# MyRIO_Breakout_Gamma2b.net
KiCad netlist of a schematic drawn in EAGLE
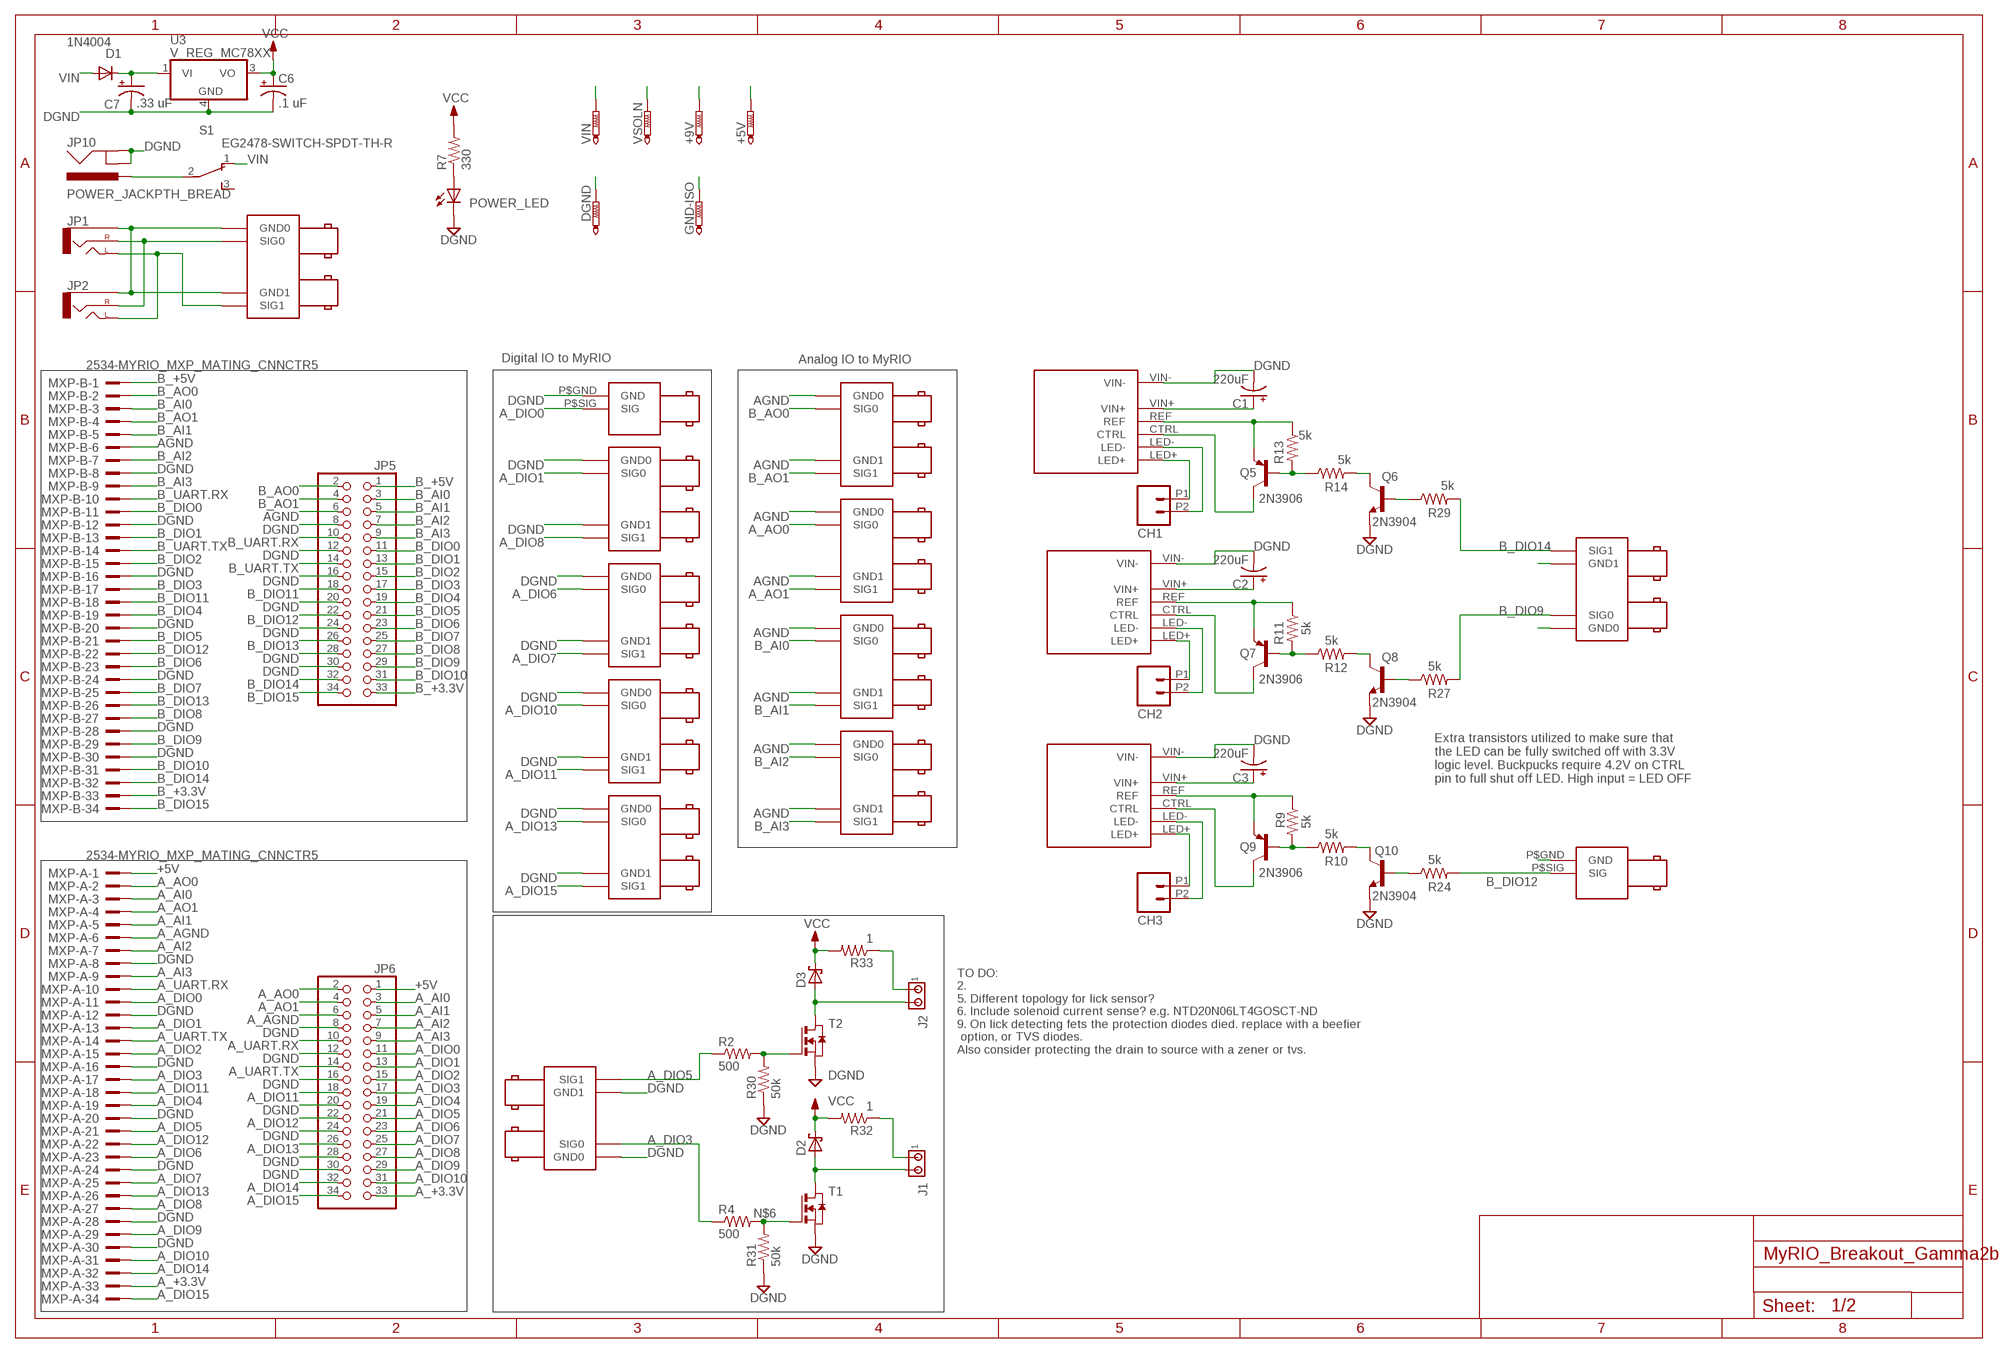
[diagram p0: schematic, sheet 1]
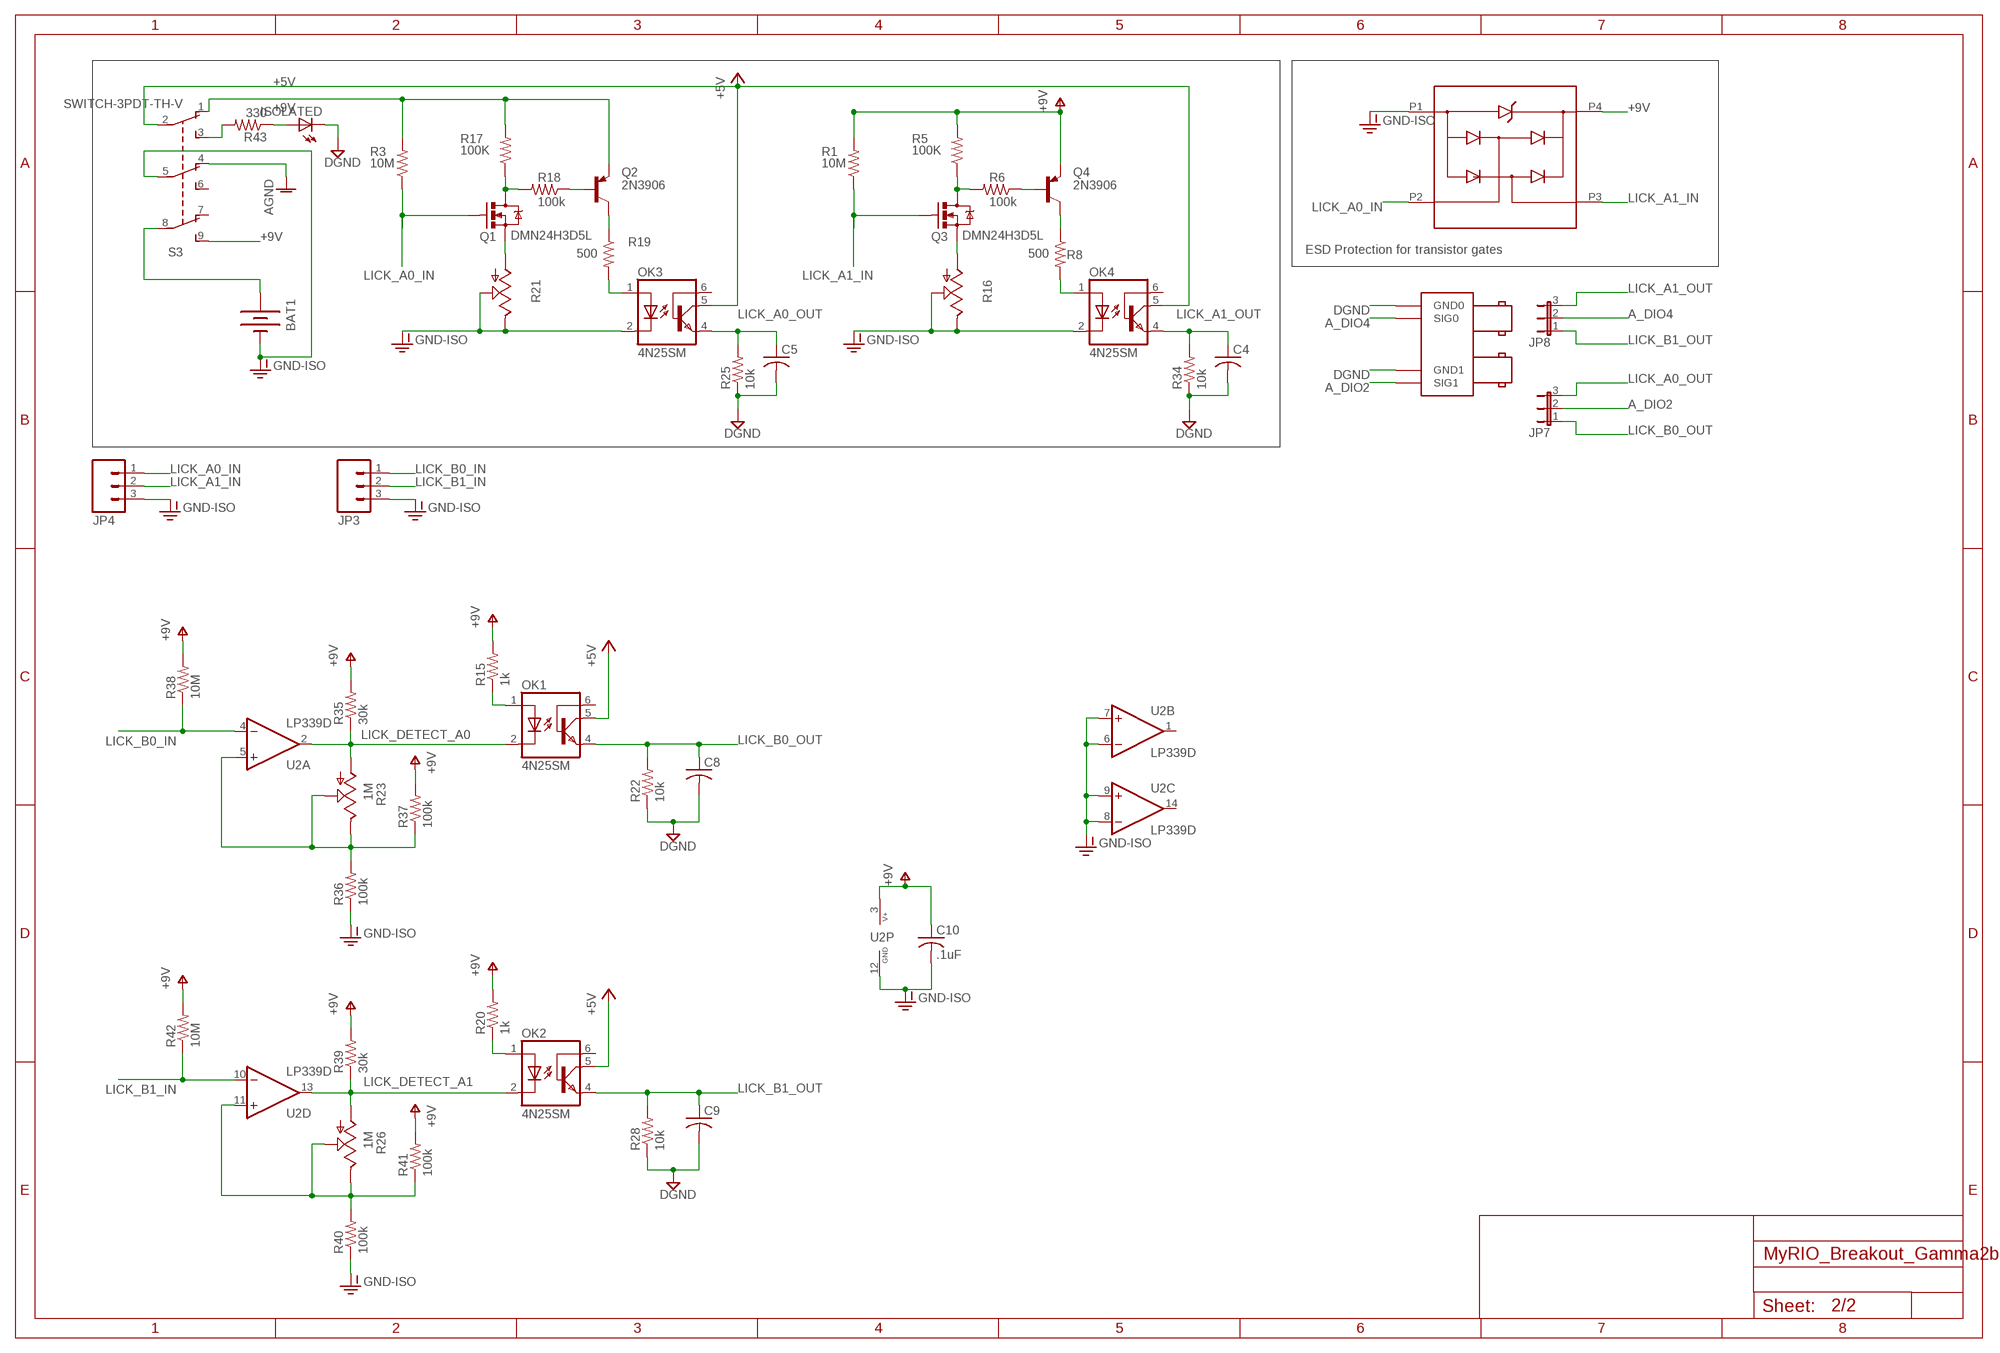
[diagram p1: schematic, sheet 2]

(export (version "E")
  (design (tool "Eeschema 10.0.6"))
  (components
    (comp (ref "BAT1")
      (value "BATTERY9V")
      (footprint "eagle-import:BATTCON_9V")
      (libsource (lib "eagle-import") (part "BATTERY9V"))
    )
    (comp (ref "C4")
      (value "C-US025-024X044")
      (footprint "eagle-import:C025-024X044")
      (libsource (lib "eagle-import") (part "C-US025-024X044"))
    )
    (comp (ref "C5")
      (value "C-US025-024X044")
      (footprint "eagle-import:C025-024X044")
      (libsource (lib "eagle-import") (part "C-US025-024X044"))
    )
    (comp (ref "C8")
      (value "C-US025-024X044")
      (footprint "eagle-import:C025-024X044")
      (libsource (lib "eagle-import") (part "C-US025-024X044"))
    )
    (comp (ref "C9")
      (value "C-US025-024X044")
      (footprint "eagle-import:C025-024X044")
      (libsource (lib "eagle-import") (part "C-US025-024X044"))
    )
    (comp (ref "C10")
      (value ".1uF")
      (footprint "eagle-import:C0805K")
      (libsource (lib "eagle-import") (part "C-USC0805K"))
    )
    (comp (ref "ISOLATED")
      (value "LED3MM")
      (footprint "eagle-import:LED3MM")
      (libsource (lib "eagle-import") (part "LED3MM"))
    )
    (comp (ref "JP3")
      (value "M03POLAR")
      (footprint "eagle-import:MOLEX-1X3")
      (libsource (lib "eagle-import") (part "M03POLAR"))
    )
    (comp (ref "JP4")
      (value "M03POLAR")
      (footprint "eagle-import:MOLEX-1X3")
      (libsource (lib "eagle-import") (part "M03POLAR"))
    )
    (comp (ref "JP7")
      (value "JP2E")
      (footprint "eagle-import:JP2")
      (libsource (lib "eagle-import") (part "JP2E"))
    )
    (comp (ref "JP8")
      (value "JP2E")
      (footprint "eagle-import:JP2")
      (libsource (lib "eagle-import") (part "JP2E"))
    )
    (comp (ref "LICK")
      (value "BNC_RIGHT_ANGLE_DOUBLE")
      (footprint "eagle-import:BNC_RIGHT_ANGLE_DOUBLE")
      (libsource (lib "eagle-import") (part "BNC_RIGHT_ANGLE_DOUBLE"))
    )
    (comp (ref "OK1")
      (value "4N25SM")
      (footprint "eagle-import:DIL6-SMD")
      (fields (field (name "MF") "FAIRCHILD SEMICONDUCTOR"))
      (libsource (lib "eagle-import") (part "4N?MS25"))
    )
    (comp (ref "OK2")
      (value "4N25SM")
      (footprint "eagle-import:DIL6-SMD")
      (fields (field (name "MF") "FAIRCHILD SEMICONDUCTOR"))
      (libsource (lib "eagle-import") (part "4N?MS25"))
    )
    (comp (ref "OK3")
      (value "4N25SM")
      (footprint "eagle-import:DIL6-SMD")
      (fields (field (name "MF") "FAIRCHILD SEMICONDUCTOR"))
      (libsource (lib "eagle-import") (part "4N?MS25"))
    )
    (comp (ref "OK4")
      (value "4N25SM")
      (footprint "eagle-import:DIL6-SMD")
      (fields (field (name "MF") "FAIRCHILD SEMICONDUCTOR"))
      (libsource (lib "eagle-import") (part "4N?MS25"))
    )
    (comp (ref "Q1")
      (value "DMN24H3D5L")
      (footprint "eagle-import:SOT23-3")
      (libsource (lib "eagle-import") (part "MOSFET-NCHANNELAO3404A"))
    )
    (comp (ref "Q2")
      (value "2N3906")
      (footprint "eagle-import:SOT23-BEC")
      (libsource (lib "eagle-import") (part "-PNP-SOT23-BECMMBT3906LT1"))
    )
    (comp (ref "Q3")
      (value "DMN24H3D5L")
      (footprint "eagle-import:SOT23-3")
      (libsource (lib "eagle-import") (part "MOSFET-NCHANNELAO3404A"))
    )
    (comp (ref "Q4")
      (value "2N3906")
      (footprint "eagle-import:SOT23-BEC")
      (libsource (lib "eagle-import") (part "-PNP-SOT23-BECMMBT3906LT1"))
    )
    (comp (ref "R1")
      (value "10M")
      (footprint "eagle-import:0805S")
      (libsource (lib "eagle-import") (part "RESISTOR_SM0805S"))
    )
    (comp (ref "R3")
      (value "10M")
      (footprint "eagle-import:0805S")
      (libsource (lib "eagle-import") (part "RESISTOR_SM0805S"))
    )
    (comp (ref "R5")
      (value "100K")
      (footprint "eagle-import:0805S")
      (libsource (lib "eagle-import") (part "RESISTOR_SM0805S"))
    )
    (comp (ref "R6")
      (value "100k")
      (footprint "eagle-import:0805S")
      (libsource (lib "eagle-import") (part "RESISTOR_SM0805S"))
    )
    (comp (ref "R8")
      (value "500")
      (footprint "eagle-import:0805S")
      (libsource (lib "eagle-import") (part "RESISTOR_SM0805S"))
    )
    (comp (ref "R15")
      (value "1k")
      (footprint "eagle-import:M0805")
      (libsource (lib "eagle-import") (part "R-US_M0805"))
    )
    (comp (ref "R16")
      (value "TRIM_US-B25P")
      (footprint "eagle-import:B25P")
      (libsource (lib "eagle-import") (part "TRIM_US-B25P"))
    )
    (comp (ref "R17")
      (value "100K")
      (footprint "eagle-import:0805S")
      (libsource (lib "eagle-import") (part "RESISTOR_SM0805S"))
    )
    (comp (ref "R18")
      (value "100k")
      (footprint "eagle-import:0805S")
      (libsource (lib "eagle-import") (part "RESISTOR_SM0805S"))
    )
    (comp (ref "R19")
      (value "500")
      (footprint "eagle-import:0805S")
      (libsource (lib "eagle-import") (part "RESISTOR_SM0805S"))
    )
    (comp (ref "R20")
      (value "1k")
      (footprint "eagle-import:M0805")
      (libsource (lib "eagle-import") (part "R-US_M0805"))
    )
    (comp (ref "R21")
      (value "TRIM_US-B25P")
      (footprint "eagle-import:B25P")
      (libsource (lib "eagle-import") (part "TRIM_US-B25P"))
    )
    (comp (ref "R22")
      (value "10k")
      (footprint "eagle-import:0204V")
      (libsource (lib "eagle-import") (part "R-US_0204/2V"))
    )
    (comp (ref "R23")
      (value "1M")
      (footprint "eagle-import:B25P")
      (libsource (lib "eagle-import") (part "TRIM_US-B25P"))
    )
    (comp (ref "R25")
      (value "10k")
      (footprint "eagle-import:0204V")
      (libsource (lib "eagle-import") (part "R-US_0204/2V"))
    )
    (comp (ref "R26")
      (value "1M")
      (footprint "eagle-import:B25P")
      (libsource (lib "eagle-import") (part "TRIM_US-B25P"))
    )
    (comp (ref "R28")
      (value "10k")
      (footprint "eagle-import:0204V")
      (libsource (lib "eagle-import") (part "R-US_0204/2V"))
    )
    (comp (ref "R34")
      (value "10k")
      (footprint "eagle-import:0204V")
      (libsource (lib "eagle-import") (part "R-US_0204/2V"))
    )
    (comp (ref "R35")
      (value "30k")
      (footprint "eagle-import:M0805")
      (libsource (lib "eagle-import") (part "R-US_M0805"))
    )
    (comp (ref "R36")
      (value "100k")
      (footprint "eagle-import:M0805")
      (libsource (lib "eagle-import") (part "R-US_M0805"))
    )
    (comp (ref "R37")
      (value "100k")
      (footprint "eagle-import:M0805")
      (libsource (lib "eagle-import") (part "R-US_M0805"))
    )
    (comp (ref "R38")
      (value "10M")
      (footprint "eagle-import:M0805")
      (libsource (lib "eagle-import") (part "R-US_M0805"))
    )
    (comp (ref "R39")
      (value "30k")
      (footprint "eagle-import:M0805")
      (libsource (lib "eagle-import") (part "R-US_M0805"))
    )
    (comp (ref "R40")
      (value "100k")
      (footprint "eagle-import:M0805")
      (libsource (lib "eagle-import") (part "R-US_M0805"))
    )
    (comp (ref "R41")
      (value "100k")
      (footprint "eagle-import:M0805")
      (libsource (lib "eagle-import") (part "R-US_M0805"))
    )
    (comp (ref "R42")
      (value "10M")
      (footprint "eagle-import:M0805")
      (libsource (lib "eagle-import") (part "R-US_M0805"))
    )
    (comp (ref "R43")
      (value "330")
      (footprint "eagle-import:0207_10")
      (libsource (lib "eagle-import") (part "R-US_0207/10"))
    )
    (comp (ref "S3")
      (value "SWITCH-3PDT-TH-V")
      (footprint "eagle-import:NKK-M20-9PIN-VERTICAL")
      (libsource (lib "eagle-import") (part "SWITCH-3PDT-TH-V"))
    )
    (comp (ref "U1")
      (value "CD143A-12_TVS")
      (footprint "eagle-import:SOT-143")
      (libsource (lib "eagle-import") (part "CD143A-12_TVS"))
    )
    (comp (ref "U2")
      (value "LP339D")
      (footprint "eagle-import:SO14")
      (libsource (lib "eagle-import") (part "LM339D"))
    )
    (comp (ref "+5V")
      (value "PTR1PAD1-17Y")
      (footprint "eagle-import:P1-17Y")
      (libsource (lib "eagle-import") (part "PTR1PAD1-17Y"))
    )
    (comp (ref "+9V")
      (value "PTR1PAD1-17Y")
      (footprint "eagle-import:P1-17Y")
      (libsource (lib "eagle-import") (part "PTR1PAD1-17Y"))
    )
    (comp (ref "AAO_0,1")
      (value "BNC_RIGHT_ANGLE_DOUBLE")
      (footprint "eagle-import:BNC_RIGHT_ANGLE_DOUBLE")
      (libsource (lib "eagle-import") (part "BNC_RIGHT_ANGLE_DOUBLE"))
    )
    (comp (ref "ACTV_REC")
      (value "BNC_RIGHT_ANGLE")
      (footprint "eagle-import:BNC_RIGHT_ANGLE")
      (libsource (lib "eagle-import") (part "BNC_RIGHT_ANGLE"))
    )
    (comp (ref "AUDIO")
      (value "BNC_RIGHT_ANGLE_DOUBLE")
      (footprint "eagle-import:BNC_RIGHT_ANGLE_DOUBLE")
      (libsource (lib "eagle-import") (part "BNC_RIGHT_ANGLE_DOUBLE"))
    )
    (comp (ref "BAI_0,1")
      (value "BNC_RIGHT_ANGLE_DOUBLE")
      (footprint "eagle-import:BNC_RIGHT_ANGLE_DOUBLE")
      (libsource (lib "eagle-import") (part "BNC_RIGHT_ANGLE_DOUBLE"))
    )
    (comp (ref "BAI_2,3")
      (value "BNC_RIGHT_ANGLE_DOUBLE")
      (footprint "eagle-import:BNC_RIGHT_ANGLE_DOUBLE")
      (libsource (lib "eagle-import") (part "BNC_RIGHT_ANGLE_DOUBLE"))
    )
    (comp (ref "BAO_0,1")
      (value "BNC_RIGHT_ANGLE_DOUBLE")
      (footprint "eagle-import:BNC_RIGHT_ANGLE_DOUBLE")
      (libsource (lib "eagle-import") (part "BNC_RIGHT_ANGLE_DOUBLE"))
    )
    (comp (ref "BUCKPUCK1")
      (value "BUCKPUCK-350-I")
      (footprint "eagle-import:BUCKPUCK_I")
      (libsource (lib "eagle-import") (part "BUCKPUCK--?I350"))
    )
    (comp (ref "BUCKPUCK2")
      (value "BUCKPUCK-350-I")
      (footprint "eagle-import:BUCKPUCK_I")
      (libsource (lib "eagle-import") (part "BUCKPUCK--?I350"))
    )
    (comp (ref "BUCKPUCK3")
      (value "BUCKPUCK-350-I")
      (footprint "eagle-import:BUCKPUCK_I")
      (libsource (lib "eagle-import") (part "BUCKPUCK--?I350"))
    )
    (comp (ref "C1")
      (value "220uF")
      (footprint "eagle-import:E5-10,5")
      (libsource (lib "eagle-import") (part "CPOL-USE5-10.5"))
    )
    (comp (ref "C2")
      (value "220uF")
      (footprint "eagle-import:E5-10,5")
      (libsource (lib "eagle-import") (part "CPOL-USE5-10.5"))
    )
    (comp (ref "C3")
      (value "220uF")
      (footprint "eagle-import:E5-10,5")
      (libsource (lib "eagle-import") (part "CPOL-USE5-10.5"))
    )
    (comp (ref "C6")
      (value ".1 uF")
      (footprint "eagle-import:E2,5-5")
      (libsource (lib "eagle-import") (part "CPOL-USE2.5-5"))
    )
    (comp (ref "C7")
      (value ".33 uF")
      (footprint "eagle-import:E2,5-5")
      (libsource (lib "eagle-import") (part "CPOL-USE2.5-5"))
    )
    (comp (ref "CAMERA")
      (value "BNC_RIGHT_ANGLE_DOUBLE")
      (footprint "eagle-import:BNC_RIGHT_ANGLE_DOUBLE")
      (libsource (lib "eagle-import") (part "BNC_RIGHT_ANGLE_DOUBLE"))
    )
    (comp (ref "CH1")
      (value "M022.54MM_SCREWTERM")
      (footprint "eagle-import:1X02_2.54_SCREWTERM")
      (libsource (lib "eagle-import") (part "M022.54MM_SCREWTERM"))
    )
    (comp (ref "CH2")
      (value "M022.54MM_SCREWTERM")
      (footprint "eagle-import:1X02_2.54_SCREWTERM")
      (libsource (lib "eagle-import") (part "M022.54MM_SCREWTERM"))
    )
    (comp (ref "CH3")
      (value "M022.54MM_SCREWTERM")
      (footprint "eagle-import:1X02_2.54_SCREWTERM")
      (libsource (lib "eagle-import") (part "M022.54MM_SCREWTERM"))
    )
    (comp (ref "D1")
      (value "1N4004")
      (footprint "eagle-import:DO41-10")
      (libsource (lib "eagle-import") (part "1N4004"))
    )
    (comp (ref "D2")
      (value "SCHOTTKY-DIODE")
      (footprint "eagle-import:DIODE_SMB")
      (libsource (lib "eagle-import") (part "SCHOTTKY-DIODE"))
    )
    (comp (ref "D3")
      (value "SCHOTTKY-DIODE")
      (footprint "eagle-import:DIODE_SMB")
      (libsource (lib "eagle-import") (part "SCHOTTKY-DIODE"))
    )
    (comp (ref "DGND")
      (value "PTR1PAD1-17Y")
      (footprint "eagle-import:P1-17Y")
      (libsource (lib "eagle-import") (part "PTR1PAD1-17Y"))
    )
    (comp (ref "D_FREE1_2")
      (value "BNC_RIGHT_ANGLE_DOUBLE")
      (footprint "eagle-import:BNC_RIGHT_ANGLE_DOUBLE")
      (libsource (lib "eagle-import") (part "BNC_RIGHT_ANGLE_DOUBLE"))
    )
    (comp (ref "D_FREE3_4")
      (value "BNC_RIGHT_ANGLE_DOUBLE")
      (footprint "eagle-import:BNC_RIGHT_ANGLE_DOUBLE")
      (libsource (lib "eagle-import") (part "BNC_RIGHT_ANGLE_DOUBLE"))
    )
    (comp (ref "GND-ISO")
      (value "PTR1PAD1-17Y")
      (footprint "eagle-import:P1-17Y")
      (libsource (lib "eagle-import") (part "PTR1PAD1-17Y"))
    )
    (comp (ref "J1")
      (value "MTA02-100")
      (footprint "eagle-import:10X02MTA")
      (libsource (lib "eagle-import") (part "MTA02-100"))
    )
    (comp (ref "J2")
      (value "MTA02-100")
      (footprint "eagle-import:10X02MTA")
      (libsource (lib "eagle-import") (part "MTA02-100"))
    )
    (comp (ref "JP1")
      (value "AUDIO-JACKPTH")
      (footprint "eagle-import:AUDIO-JACK")
      (libsource (lib "eagle-import") (part "AUDIO-JACKPTH"))
    )
    (comp (ref "JP2")
      (value "AUDIO-JACKPTH")
      (footprint "eagle-import:AUDIO-JACK")
      (libsource (lib "eagle-import") (part "AUDIO-JACKPTH"))
    )
    (comp (ref "JP5")
      (value "PINHD-2X17")
      (footprint "eagle-import:2X17")
      (libsource (lib "eagle-import") (part "PINHD-2X17"))
    )
    (comp (ref "JP6")
      (value "PINHD-2X17")
      (footprint "eagle-import:2X17")
      (libsource (lib "eagle-import") (part "PINHD-2X17"))
    )
    (comp (ref "JP10")
      (value "POWER_JACKPTH_BREAD")
      (footprint "eagle-import:POWER_JACK_PTH_BREAD")
      (libsource (lib "eagle-import") (part "POWER_JACKPTH_BREAD"))
    )
    (comp (ref "LED_CUE")
      (value "BNC_RIGHT_ANGLE")
      (footprint "eagle-import:BNC_RIGHT_ANGLE")
      (libsource (lib "eagle-import") (part "BNC_RIGHT_ANGLE"))
    )
    (comp (ref "LED_MASK")
      (value "BNC_RIGHT_ANGLE_DOUBLE")
      (footprint "eagle-import:BNC_RIGHT_ANGLE_DOUBLE")
      (libsource (lib "eagle-import") (part "BNC_RIGHT_ANGLE_DOUBLE"))
    )
    (comp (ref "MXP-A")
      (value "2534-MYRIO_MXP_MATING_CNNCTR5")
      (footprint "eagle-import:PAK100_2500-5-34-MXP_CONNCTR")
      (libsource (lib "eagle-import") (part "2534-MYRIO_MXP_MATING_CNNCTR5"))
    )
    (comp (ref "MXP-B")
      (value "2534-MYRIO_MXP_MATING_CNNCTR5")
      (footprint "eagle-import:PAK100_2500-5-34-MXP_CONNCTR")
      (libsource (lib "eagle-import") (part "2534-MYRIO_MXP_MATING_CNNCTR5"))
    )
    (comp (ref "POWER_LED")
      (value "LED3MM")
      (footprint "eagle-import:LED3MM")
      (libsource (lib "eagle-import") (part "LED3MM"))
    )
    (comp (ref "Q5")
      (value "2N3906")
      (footprint "eagle-import:SOT23-BEC")
      (libsource (lib "eagle-import") (part "-PNP-SOT23-BECMMBT3906LT1"))
    )
    (comp (ref "Q6")
      (value "2N3904")
      (footprint "eagle-import:SOT23-BEC")
      (libsource (lib "eagle-import") (part "-NPN-SOT23-BECMMBT3904LT1"))
    )
    (comp (ref "Q7")
      (value "2N3906")
      (footprint "eagle-import:SOT23-BEC")
      (libsource (lib "eagle-import") (part "-PNP-SOT23-BECMMBT3906LT1"))
    )
    (comp (ref "Q8")
      (value "2N3904")
      (footprint "eagle-import:SOT23-BEC")
      (libsource (lib "eagle-import") (part "-NPN-SOT23-BECMMBT3904LT1"))
    )
    (comp (ref "Q9")
      (value "2N3906")
      (footprint "eagle-import:SOT23-BEC")
      (libsource (lib "eagle-import") (part "-PNP-SOT23-BECMMBT3906LT1"))
    )
    (comp (ref "Q10")
      (value "2N3904")
      (footprint "eagle-import:SOT23-BEC")
      (libsource (lib "eagle-import") (part "-NPN-SOT23-BECMMBT3904LT1"))
    )
    (comp (ref "R2")
      (value "500")
      (footprint "eagle-import:M1206")
      (libsource (lib "eagle-import") (part "R-US_M1206"))
    )
    (comp (ref "R4")
      (value "500")
      (footprint "eagle-import:M1206")
      (libsource (lib "eagle-import") (part "R-US_M1206"))
    )
    (comp (ref "R7")
      (value "330")
      (footprint "eagle-import:0207_10")
      (libsource (lib "eagle-import") (part "R-US_0207/10"))
    )
    (comp (ref "R9")
      (value "5k")
      (footprint "eagle-import:0805S")
      (libsource (lib "eagle-import") (part "RESISTOR_SM0805S"))
    )
    (comp (ref "R10")
      (value "5k")
      (footprint "eagle-import:0805S")
      (libsource (lib "eagle-import") (part "RESISTOR_SM0805S"))
    )
    (comp (ref "R11")
      (value "5k")
      (footprint "eagle-import:0805S")
      (libsource (lib "eagle-import") (part "RESISTOR_SM0805S"))
    )
    (comp (ref "R12")
      (value "5k")
      (footprint "eagle-import:0805S")
      (libsource (lib "eagle-import") (part "RESISTOR_SM0805S"))
    )
    (comp (ref "R13")
      (value "5k")
      (footprint "eagle-import:0805S")
      (libsource (lib "eagle-import") (part "RESISTOR_SM0805S"))
    )
    (comp (ref "R14")
      (value "5k")
      (footprint "eagle-import:0805S")
      (libsource (lib "eagle-import") (part "RESISTOR_SM0805S"))
    )
    (comp (ref "R24")
      (value "5k")
      (footprint "eagle-import:0805S")
      (libsource (lib "eagle-import") (part "RESISTOR_SM0805S"))
    )
    (comp (ref "R27")
      (value "5k")
      (footprint "eagle-import:0805S")
      (libsource (lib "eagle-import") (part "RESISTOR_SM0805S"))
    )
    (comp (ref "R29")
      (value "5k")
      (footprint "eagle-import:0805S")
      (libsource (lib "eagle-import") (part "RESISTOR_SM0805S"))
    )
    (comp (ref "R30")
      (value "50k")
      (footprint "eagle-import:M1206")
      (libsource (lib "eagle-import") (part "R-US_M1206"))
    )
    (comp (ref "R31")
      (value "50k")
      (footprint "eagle-import:M1206")
      (libsource (lib "eagle-import") (part "R-US_M1206"))
    )
    (comp (ref "R32")
      (value "1")
      (footprint "eagle-import:M1206")
      (libsource (lib "eagle-import") (part "R-US_M1206"))
    )
    (comp (ref "R33")
      (value "1")
      (footprint "eagle-import:M1206")
      (libsource (lib "eagle-import") (part "R-US_M1206"))
    )
    (comp (ref "S1")
      (value "EG2478-SWITCH-SPDT-TH-R")
      (footprint "eagle-import:ESWITCH_500-SSP1M6")
      (libsource (lib "eagle-import") (part "EG2478-SWITCH-SPDT-TH-R"))
    )
    (comp (ref "SHUTTER")
      (value "BNC_RIGHT_ANGLE_DOUBLE")
      (footprint "eagle-import:BNC_RIGHT_ANGLE_DOUBLE")
      (libsource (lib "eagle-import") (part "BNC_RIGHT_ANGLE_DOUBLE"))
    )
    (comp (ref "SLN")
      (value "BNC_RIGHT_ANGLE_DOUBLE")
      (footprint "eagle-import:BNC_RIGHT_ANGLE_DOUBLE")
      (libsource (lib "eagle-import") (part "BNC_RIGHT_ANGLE_DOUBLE"))
    )
    (comp (ref "T1")
      (value "NMOSSOT223")
      (footprint "eagle-import:SOT223")
      (libsource (lib "eagle-import") (part "NMOSSOT223"))
    )
    (comp (ref "T2")
      (value "NMOSSOT223")
      (footprint "eagle-import:SOT223")
      (libsource (lib "eagle-import") (part "NMOSSOT223"))
    )
    (comp (ref "U3")
      (value "V_REG_MC78XX")
      (footprint "eagle-import:DPAK")
      (libsource (lib "eagle-import") (part "V_REG_MC78XX"))
    )
    (comp (ref "VIN")
      (value "PTR1PAD1-17Y")
      (footprint "eagle-import:P1-17Y")
      (libsource (lib "eagle-import") (part "PTR1PAD1-17Y"))
    )
    (comp (ref "VSOLN")
      (value "PTR1PAD1-17Y")
      (footprint "eagle-import:P1-17Y")
      (libsource (lib "eagle-import") (part "PTR1PAD1-17Y"))
    )
  )
  (nets
    (net (code "1") (name "+5V") (class "Default")
      (node (ref "+5V") (pin "TP") (pinfunction "TP_TP") (pintype "input"))
      (node (ref "JP6") (pin "1") (pinfunction "1_1") (pintype "passive"))
      (node (ref "MXP-A") (pin "1") (pinfunction "KL_1") (pintype "passive"))
      (node (ref "OK1") (pin "5") (pinfunction "COL_5") (pintype "passive"))
      (node (ref "OK2") (pin "5") (pinfunction "COL_5") (pintype "passive"))
      (node (ref "OK3") (pin "5") (pinfunction "COL_5") (pintype "passive"))
      (node (ref "OK4") (pin "5") (pinfunction "COL_5") (pintype "passive"))
      (node (ref "S3") (pin "2") (pinfunction "P1_2") (pintype "passive"))
    )
    (net (code "2") (name "+9V") (class "Default")
      (node (ref "+9V") (pin "TP") (pinfunction "TP_TP") (pintype "input"))
      (node (ref "C10") (pin "1") (pinfunction "1_1") (pintype "passive"))
      (node (ref "Q2") (pin "E") (pinfunction "E_E") (pintype "passive"))
      (node (ref "Q4") (pin "E") (pinfunction "E_E") (pintype "passive"))
      (node (ref "R1") (pin "2") (pinfunction "2_2") (pintype "passive"))
      (node (ref "R15") (pin "2") (pinfunction "2_2") (pintype "passive"))
      (node (ref "R17") (pin "2") (pinfunction "2_2") (pintype "passive"))
      (node (ref "R20") (pin "2") (pinfunction "2_2") (pintype "passive"))
      (node (ref "R3") (pin "2") (pinfunction "2_2") (pintype "passive"))
      (node (ref "R35") (pin "2") (pinfunction "2_2") (pintype "passive"))
      (node (ref "R37") (pin "2") (pinfunction "2_2") (pintype "passive"))
      (node (ref "R38") (pin "2") (pinfunction "2_2") (pintype "passive"))
      (node (ref "R39") (pin "2") (pinfunction "2_2") (pintype "passive"))
      (node (ref "R41") (pin "2") (pinfunction "2_2") (pintype "passive"))
      (node (ref "R42") (pin "2") (pinfunction "2_2") (pintype "passive"))
      (node (ref "R5") (pin "2") (pinfunction "2_2") (pintype "passive"))
      (node (ref "S3") (pin "1") (pinfunction "O1_1") (pintype "passive"))
      (node (ref "S3") (pin "9") (pinfunction "S3_9") (pintype "passive"))
      (node (ref "U1") (pin "P4") (pinfunction "P$4_P4") (pintype "bidirectional"))
      (node (ref "U2") (pin "3") (pinfunction "V+_3") (pintype "power_in"))
    )
    (net (code "3") (name "AGND") (class "Default")
      (node (ref "AAO_0,1") (pin "P$GND0") (pinfunction "GND0_P$GND0") (pintype "bidirectional"))
      (node (ref "AAO_0,1") (pin "P$GND1") (pinfunction "GND1_P$GND1") (pintype "bidirectional"))
      (node (ref "BAI_0,1") (pin "P$GND0") (pinfunction "GND0_P$GND0") (pintype "bidirectional"))
      (node (ref "BAI_0,1") (pin "P$GND1") (pinfunction "GND1_P$GND1") (pintype "bidirectional"))
      (node (ref "BAI_2,3") (pin "P$GND0") (pinfunction "GND0_P$GND0") (pintype "bidirectional"))
      (node (ref "BAI_2,3") (pin "P$GND1") (pinfunction "GND1_P$GND1") (pintype "bidirectional"))
      (node (ref "BAO_0,1") (pin "P$GND0") (pinfunction "GND0_P$GND0") (pintype "bidirectional"))
      (node (ref "BAO_0,1") (pin "P$GND1") (pinfunction "GND1_P$GND1") (pintype "bidirectional"))
      (node (ref "JP5") (pin "6") (pinfunction "6_6") (pintype "passive"))
      (node (ref "MXP-B") (pin "6") (pinfunction "KL_6") (pintype "passive"))
      (node (ref "S3") (pin "4") (pinfunction "O2_4") (pintype "passive"))
    )
    (net (code "4") (name "A_+3.3V") (class "Default")
      (node (ref "JP6") (pin "33") (pinfunction "33_33") (pintype "passive"))
      (node (ref "MXP-A") (pin "33") (pinfunction "KL_33") (pintype "passive"))
    )
    (net (code "5") (name "A_AGND") (class "Default")
      (node (ref "JP6") (pin "6") (pinfunction "6_6") (pintype "passive"))
      (node (ref "MXP-A") (pin "6") (pinfunction "KL_6") (pintype "passive"))
    )
    (net (code "6") (name "A_AI0") (class "Default")
      (node (ref "JP6") (pin "3") (pinfunction "3_3") (pintype "passive"))
      (node (ref "MXP-A") (pin "3") (pinfunction "KL_3") (pintype "passive"))
    )
    (net (code "7") (name "A_AI1") (class "Default")
      (node (ref "JP6") (pin "5") (pinfunction "5_5") (pintype "passive"))
      (node (ref "MXP-A") (pin "5") (pinfunction "KL_5") (pintype "passive"))
    )
    (net (code "8") (name "A_AI2") (class "Default")
      (node (ref "JP6") (pin "7") (pinfunction "7_7") (pintype "passive"))
      (node (ref "MXP-A") (pin "7") (pinfunction "KL_7") (pintype "passive"))
    )
    (net (code "9") (name "A_AI3") (class "Default")
      (node (ref "JP6") (pin "9") (pinfunction "9_9") (pintype "passive"))
      (node (ref "MXP-A") (pin "9") (pinfunction "KL_9") (pintype "passive"))
    )
    (net (code "10") (name "A_AO0") (class "Default")
      (node (ref "AAO_0,1") (pin "P$SIG0") (pinfunction "SIG0_P$SIG0") (pintype "bidirectional"))
      (node (ref "JP6") (pin "2") (pinfunction "2_2") (pintype "passive"))
      (node (ref "MXP-A") (pin "2") (pinfunction "KL_2") (pintype "passive"))
    )
    (net (code "11") (name "A_AO1") (class "Default")
      (node (ref "AAO_0,1") (pin "P$SIG1") (pinfunction "SIG1_P$SIG1") (pintype "bidirectional"))
      (node (ref "JP6") (pin "4") (pinfunction "4_4") (pintype "passive"))
      (node (ref "MXP-A") (pin "4") (pinfunction "KL_4") (pintype "passive"))
    )
    (net (code "12") (name "A_DIO0") (class "Default")
      (node (ref "ACTV_REC") (pin "P$SIG") (pinfunction "SIG_P$SIG") (pintype "bidirectional"))
      (node (ref "JP6") (pin "11") (pinfunction "11_11") (pintype "passive"))
      (node (ref "MXP-A") (pin "11") (pinfunction "KL_11") (pintype "passive"))
    )
    (net (code "13") (name "A_DIO1") (class "Default")
      (node (ref "CAMERA") (pin "P$SIG0") (pinfunction "SIG0_P$SIG0") (pintype "bidirectional"))
      (node (ref "JP6") (pin "13") (pinfunction "13_13") (pintype "passive"))
      (node (ref "MXP-A") (pin "13") (pinfunction "KL_13") (pintype "passive"))
    )
    (net (code "14") (name "A_DIO2") (class "Default")
      (node (ref "JP6") (pin "15") (pinfunction "15_15") (pintype "passive"))
      (node (ref "JP7") (pin "2") (pinfunction "2_2") (pintype "passive"))
      (node (ref "LICK") (pin "P$SIG1") (pinfunction "SIG1_P$SIG1") (pintype "bidirectional"))
      (node (ref "MXP-A") (pin "15") (pinfunction "KL_15") (pintype "passive"))
    )
    (net (code "15") (name "A_DIO3") (class "Default")
      (node (ref "JP6") (pin "17") (pinfunction "17_17") (pintype "passive"))
      (node (ref "MXP-A") (pin "17") (pinfunction "KL_17") (pintype "passive"))
      (node (ref "R4") (pin "1") (pinfunction "1_1") (pintype "passive"))
      (node (ref "SLN") (pin "P$SIG0") (pinfunction "SIG0_P$SIG0") (pintype "bidirectional"))
    )
    (net (code "16") (name "A_DIO4") (class "Default")
      (node (ref "JP6") (pin "19") (pinfunction "19_19") (pintype "passive"))
      (node (ref "JP8") (pin "2") (pinfunction "2_2") (pintype "passive"))
      (node (ref "LICK") (pin "P$SIG0") (pinfunction "SIG0_P$SIG0") (pintype "bidirectional"))
      (node (ref "MXP-A") (pin "19") (pinfunction "KL_19") (pintype "passive"))
    )
    (net (code "17") (name "A_DIO5") (class "Default")
      (node (ref "JP6") (pin "21") (pinfunction "21_21") (pintype "passive"))
      (node (ref "MXP-A") (pin "21") (pinfunction "KL_21") (pintype "passive"))
      (node (ref "R2") (pin "1") (pinfunction "1_1") (pintype "passive"))
      (node (ref "SLN") (pin "P$SIG1") (pinfunction "SIG1_P$SIG1") (pintype "bidirectional"))
    )
    (net (code "18") (name "A_DIO6") (class "Default")
      (node (ref "JP6") (pin "23") (pinfunction "23_23") (pintype "passive"))
      (node (ref "MXP-A") (pin "23") (pinfunction "KL_23") (pintype "passive"))
      (node (ref "SHUTTER") (pin "P$SIG0") (pinfunction "SIG0_P$SIG0") (pintype "bidirectional"))
    )
    (net (code "19") (name "A_DIO7") (class "Default")
      (node (ref "JP6") (pin "25") (pinfunction "25_25") (pintype "passive"))
      (node (ref "MXP-A") (pin "25") (pinfunction "KL_25") (pintype "passive"))
      (node (ref "SHUTTER") (pin "P$SIG1") (pinfunction "SIG1_P$SIG1") (pintype "bidirectional"))
    )
    (net (code "20") (name "A_DIO8") (class "Default")
      (node (ref "CAMERA") (pin "P$SIG1") (pinfunction "SIG1_P$SIG1") (pintype "bidirectional"))
      (node (ref "JP6") (pin "27") (pinfunction "27_27") (pintype "passive"))
      (node (ref "MXP-A") (pin "27") (pinfunction "KL_27") (pintype "passive"))
    )
    (net (code "21") (name "A_DIO9") (class "Default")
      (node (ref "JP6") (pin "29") (pinfunction "29_29") (pintype "passive"))
      (node (ref "MXP-A") (pin "29") (pinfunction "KL_29") (pintype "passive"))
    )
    (net (code "22") (name "A_DIO10") (class "Default")
      (node (ref "D_FREE1_2") (pin "P$SIG0") (pinfunction "SIG0_P$SIG0") (pintype "bidirectional"))
      (node (ref "JP6") (pin "31") (pinfunction "31_31") (pintype "passive"))
      (node (ref "MXP-A") (pin "31") (pinfunction "KL_31") (pintype "passive"))
    )
    (net (code "23") (name "A_DIO11") (class "Default")
      (node (ref "D_FREE1_2") (pin "P$SIG1") (pinfunction "SIG1_P$SIG1") (pintype "bidirectional"))
      (node (ref "JP6") (pin "18") (pinfunction "18_18") (pintype "passive"))
      (node (ref "MXP-A") (pin "18") (pinfunction "KL_18") (pintype "passive"))
    )
    (net (code "24") (name "A_DIO12") (class "Default")
      (node (ref "JP6") (pin "22") (pinfunction "22_22") (pintype "passive"))
      (node (ref "MXP-A") (pin "22") (pinfunction "KL_22") (pintype "passive"))
    )
    (net (code "25") (name "A_DIO13") (class "Default")
      (node (ref "D_FREE3_4") (pin "P$SIG0") (pinfunction "SIG0_P$SIG0") (pintype "bidirectional"))
      (node (ref "JP6") (pin "26") (pinfunction "26_26") (pintype "passive"))
      (node (ref "MXP-A") (pin "26") (pinfunction "KL_26") (pintype "passive"))
    )
    (net (code "26") (name "A_DIO14") (class "Default")
      (node (ref "JP6") (pin "32") (pinfunction "32_32") (pintype "passive"))
      (node (ref "MXP-A") (pin "32") (pinfunction "KL_32") (pintype "passive"))
    )
    (net (code "27") (name "A_DIO15") (class "Default")
      (node (ref "D_FREE3_4") (pin "P$SIG1") (pinfunction "SIG1_P$SIG1") (pintype "bidirectional"))
      (node (ref "JP6") (pin "34") (pinfunction "34_34") (pintype "passive"))
      (node (ref "MXP-A") (pin "34") (pinfunction "KL_34") (pintype "passive"))
    )
    (net (code "28") (name "A_UART.RX") (class "Default")
      (node (ref "JP6") (pin "10") (pinfunction "10_10") (pintype "passive"))
      (node (ref "MXP-A") (pin "10") (pinfunction "KL_10") (pintype "passive"))
    )
    (net (code "29") (name "A_UART.TX") (class "Default")
      (node (ref "JP6") (pin "14") (pinfunction "14_14") (pintype "passive"))
      (node (ref "MXP-A") (pin "14") (pinfunction "KL_14") (pintype "passive"))
    )
    (net (code "30") (name "B_+3.3V") (class "Default")
      (node (ref "JP5") (pin "33") (pinfunction "33_33") (pintype "passive"))
      (node (ref "MXP-B") (pin "33") (pinfunction "KL_33") (pintype "passive"))
    )
    (net (code "31") (name "B_+5V") (class "Default")
      (node (ref "JP5") (pin "1") (pinfunction "1_1") (pintype "passive"))
      (node (ref "MXP-B") (pin "1") (pinfunction "KL_1") (pintype "passive"))
    )
    (net (code "32") (name "B_AI0") (class "Default")
      (node (ref "BAI_0,1") (pin "P$SIG0") (pinfunction "SIG0_P$SIG0") (pintype "bidirectional"))
      (node (ref "JP5") (pin "3") (pinfunction "3_3") (pintype "passive"))
      (node (ref "MXP-B") (pin "3") (pinfunction "KL_3") (pintype "passive"))
    )
    (net (code "33") (name "B_AI1") (class "Default")
      (node (ref "BAI_0,1") (pin "P$SIG1") (pinfunction "SIG1_P$SIG1") (pintype "bidirectional"))
      (node (ref "JP5") (pin "5") (pinfunction "5_5") (pintype "passive"))
      (node (ref "MXP-B") (pin "5") (pinfunction "KL_5") (pintype "passive"))
    )
    (net (code "34") (name "B_AI2") (class "Default")
      (node (ref "BAI_2,3") (pin "P$SIG0") (pinfunction "SIG0_P$SIG0") (pintype "bidirectional"))
      (node (ref "JP5") (pin "7") (pinfunction "7_7") (pintype "passive"))
      (node (ref "MXP-B") (pin "7") (pinfunction "KL_7") (pintype "passive"))
    )
    (net (code "35") (name "B_AI3") (class "Default")
      (node (ref "BAI_2,3") (pin "P$SIG1") (pinfunction "SIG1_P$SIG1") (pintype "bidirectional"))
      (node (ref "JP5") (pin "9") (pinfunction "9_9") (pintype "passive"))
      (node (ref "MXP-B") (pin "9") (pinfunction "KL_9") (pintype "passive"))
    )
    (net (code "36") (name "B_AO0") (class "Default")
      (node (ref "BAO_0,1") (pin "P$SIG0") (pinfunction "SIG0_P$SIG0") (pintype "bidirectional"))
      (node (ref "JP5") (pin "2") (pinfunction "2_2") (pintype "passive"))
      (node (ref "MXP-B") (pin "2") (pinfunction "KL_2") (pintype "passive"))
    )
    (net (code "37") (name "B_AO1") (class "Default")
      (node (ref "BAO_0,1") (pin "P$SIG1") (pinfunction "SIG1_P$SIG1") (pintype "bidirectional"))
      (node (ref "JP5") (pin "4") (pinfunction "4_4") (pintype "passive"))
      (node (ref "MXP-B") (pin "4") (pinfunction "KL_4") (pintype "passive"))
    )
    (net (code "38") (name "B_DIO0") (class "Default")
      (node (ref "JP5") (pin "11") (pinfunction "11_11") (pintype "passive"))
      (node (ref "MXP-B") (pin "11") (pinfunction "KL_11") (pintype "passive"))
    )
    (net (code "39") (name "B_DIO1") (class "Default")
      (node (ref "JP5") (pin "13") (pinfunction "13_13") (pintype "passive"))
      (node (ref "MXP-B") (pin "13") (pinfunction "KL_13") (pintype "passive"))
    )
    (net (code "40") (name "B_DIO2") (class "Default")
      (node (ref "JP5") (pin "15") (pinfunction "15_15") (pintype "passive"))
      (node (ref "MXP-B") (pin "15") (pinfunction "KL_15") (pintype "passive"))
    )
    (net (code "41") (name "B_DIO3") (class "Default")
      (node (ref "JP5") (pin "17") (pinfunction "17_17") (pintype "passive"))
      (node (ref "MXP-B") (pin "17") (pinfunction "KL_17") (pintype "passive"))
    )
    (net (code "42") (name "B_DIO4") (class "Default")
      (node (ref "JP5") (pin "19") (pinfunction "19_19") (pintype "passive"))
      (node (ref "MXP-B") (pin "19") (pinfunction "KL_19") (pintype "passive"))
    )
    (net (code "43") (name "B_DIO5") (class "Default")
      (node (ref "JP5") (pin "21") (pinfunction "21_21") (pintype "passive"))
      (node (ref "MXP-B") (pin "21") (pinfunction "KL_21") (pintype "passive"))
    )
    (net (code "44") (name "B_DIO6") (class "Default")
      (node (ref "JP5") (pin "23") (pinfunction "23_23") (pintype "passive"))
      (node (ref "MXP-B") (pin "23") (pinfunction "KL_23") (pintype "passive"))
    )
    (net (code "45") (name "B_DIO7") (class "Default")
      (node (ref "JP5") (pin "25") (pinfunction "25_25") (pintype "passive"))
      (node (ref "MXP-B") (pin "25") (pinfunction "KL_25") (pintype "passive"))
    )
    (net (code "46") (name "B_DIO8") (class "Default")
      (node (ref "JP5") (pin "27") (pinfunction "27_27") (pintype "passive"))
      (node (ref "MXP-B") (pin "27") (pinfunction "KL_27") (pintype "passive"))
    )
    (net (code "47") (name "B_DIO9") (class "Default")
      (node (ref "JP5") (pin "29") (pinfunction "29_29") (pintype "passive"))
      (node (ref "LED_MASK") (pin "P$SIG0") (pinfunction "SIG0_P$SIG0") (pintype "bidirectional"))
      (node (ref "MXP-B") (pin "29") (pinfunction "KL_29") (pintype "passive"))
      (node (ref "R27") (pin "2") (pinfunction "2_2") (pintype "passive"))
    )
    (net (code "48") (name "B_DIO10") (class "Default")
      (node (ref "JP5") (pin "31") (pinfunction "31_31") (pintype "passive"))
      (node (ref "MXP-B") (pin "31") (pinfunction "KL_31") (pintype "passive"))
    )
    (net (code "49") (name "B_DIO11") (class "Default")
      (node (ref "JP5") (pin "18") (pinfunction "18_18") (pintype "passive"))
      (node (ref "MXP-B") (pin "18") (pinfunction "KL_18") (pintype "passive"))
    )
    (net (code "50") (name "B_DIO12") (class "Default")
      (node (ref "JP5") (pin "22") (pinfunction "22_22") (pintype "passive"))
      (node (ref "LED_CUE") (pin "P$SIG") (pinfunction "SIG_P$SIG") (pintype "bidirectional"))
      (node (ref "MXP-B") (pin "22") (pinfunction "KL_22") (pintype "passive"))
      (node (ref "R24") (pin "2") (pinfunction "2_2") (pintype "passive"))
    )
    (net (code "51") (name "B_DIO13") (class "Default")
      (node (ref "JP5") (pin "26") (pinfunction "26_26") (pintype "passive"))
      (node (ref "MXP-B") (pin "26") (pinfunction "KL_26") (pintype "passive"))
    )
    (net (code "52") (name "B_DIO14") (class "Default")
      (node (ref "JP5") (pin "32") (pinfunction "32_32") (pintype "passive"))
      (node (ref "LED_MASK") (pin "P$SIG1") (pinfunction "SIG1_P$SIG1") (pintype "bidirectional"))
      (node (ref "MXP-B") (pin "32") (pinfunction "KL_32") (pintype "passive"))
      (node (ref "R29") (pin "2") (pinfunction "2_2") (pintype "passive"))
    )
    (net (code "53") (name "B_DIO15") (class "Default")
      (node (ref "JP5") (pin "34") (pinfunction "34_34") (pintype "passive"))
      (node (ref "MXP-B") (pin "34") (pinfunction "KL_34") (pintype "passive"))
    )
    (net (code "54") (name "B_UART.RX") (class "Default")
      (node (ref "JP5") (pin "10") (pinfunction "10_10") (pintype "passive"))
      (node (ref "MXP-B") (pin "10") (pinfunction "KL_10") (pintype "passive"))
    )
    (net (code "55") (name "B_UART.TX") (class "Default")
      (node (ref "JP5") (pin "14") (pinfunction "14_14") (pintype "passive"))
      (node (ref "MXP-B") (pin "14") (pinfunction "KL_14") (pintype "passive"))
    )
    (net (code "56") (name "DGND") (class "Default")
      (node (ref "ACTV_REC") (pin "P$GND") (pinfunction "GND_P$GND") (pintype "bidirectional"))
      (node (ref "BUCKPUCK1") (pin "LED-") (pinfunction "LED-_LED-") (pintype "bidirectional"))
      (node (ref "BUCKPUCK1") (pin "VIN-") (pinfunction "VIN-_VIN-") (pintype "bidirectional"))
      (node (ref "BUCKPUCK2") (pin "LED-") (pinfunction "LED-_LED-") (pintype "bidirectional"))
      (node (ref "BUCKPUCK2") (pin "VIN-") (pinfunction "VIN-_VIN-") (pintype "bidirectional"))
      (node (ref "BUCKPUCK3") (pin "LED-") (pinfunction "LED-_LED-") (pintype "bidirectional"))
      (node (ref "BUCKPUCK3") (pin "VIN-") (pinfunction "VIN-_VIN-") (pintype "bidirectional"))
      (node (ref "C1") (pin "-") (pinfunction "-_-") (pintype "passive"))
      (node (ref "C2") (pin "-") (pinfunction "-_-") (pintype "passive"))
      (node (ref "C3") (pin "-") (pinfunction "-_-") (pintype "passive"))
      (node (ref "C4") (pin "2") (pinfunction "2_2") (pintype "passive"))
      (node (ref "C5") (pin "2") (pinfunction "2_2") (pintype "passive"))
      (node (ref "C6") (pin "-") (pinfunction "-_-") (pintype "passive"))
      (node (ref "C7") (pin "-") (pinfunction "-_-") (pintype "passive"))
      (node (ref "C8") (pin "2") (pinfunction "2_2") (pintype "passive"))
      (node (ref "C9") (pin "2") (pinfunction "2_2") (pintype "passive"))
      (node (ref "CAMERA") (pin "P$GND0") (pinfunction "GND0_P$GND0") (pintype "bidirectional"))
      (node (ref "CAMERA") (pin "P$GND1") (pinfunction "GND1_P$GND1") (pintype "bidirectional"))
      (node (ref "CH1") (pin "P2") (pinfunction "2_P2") (pintype "passive"))
      (node (ref "CH2") (pin "P2") (pinfunction "2_P2") (pintype "passive"))
      (node (ref "CH3") (pin "P2") (pinfunction "2_P2") (pintype "passive"))
      (node (ref "DGND") (pin "TP") (pinfunction "TP_TP") (pintype "input"))
      (node (ref "D_FREE1_2") (pin "P$GND0") (pinfunction "GND0_P$GND0") (pintype "bidirectional"))
      (node (ref "D_FREE1_2") (pin "P$GND1") (pinfunction "GND1_P$GND1") (pintype "bidirectional"))
      (node (ref "D_FREE3_4") (pin "P$GND0") (pinfunction "GND0_P$GND0") (pintype "bidirectional"))
      (node (ref "D_FREE3_4") (pin "P$GND1") (pinfunction "GND1_P$GND1") (pintype "bidirectional"))
      (node (ref "ISOLATED") (pin "K") (pinfunction "C_K") (pintype "passive"))
      (node (ref "JP10") (pin "GND") (pinfunction "GND_GND") (pintype "bidirectional"))
      (node (ref "JP10") (pin "GNDBREAK") (pinfunction "GNDBREAK_GNDBREAK") (pintype "bidirectional"))
      (node (ref "JP5") (pin "12") (pinfunction "12_12") (pintype "passive"))
      (node (ref "JP5") (pin "16") (pinfunction "16_16") (pintype "passive"))
      (node (ref "JP5") (pin "20") (pinfunction "20_20") (pintype "passive"))
      (node (ref "JP5") (pin "24") (pinfunction "24_24") (pintype "passive"))
      (node (ref "JP5") (pin "28") (pinfunction "28_28") (pintype "passive"))
      (node (ref "JP5") (pin "30") (pinfunction "30_30") (pintype "passive"))
      (node (ref "JP5") (pin "8") (pinfunction "8_8") (pintype "passive"))
      (node (ref "JP6") (pin "12") (pinfunction "12_12") (pintype "passive"))
      (node (ref "JP6") (pin "16") (pinfunction "16_16") (pintype "passive"))
      (node (ref "JP6") (pin "20") (pinfunction "20_20") (pintype "passive"))
      (node (ref "JP6") (pin "24") (pinfunction "24_24") (pintype "passive"))
      (node (ref "JP6") (pin "28") (pinfunction "28_28") (pintype "passive"))
      (node (ref "JP6") (pin "30") (pinfunction "30_30") (pintype "passive"))
      (node (ref "JP6") (pin "8") (pinfunction "8_8") (pintype "passive"))
      (node (ref "LED_CUE") (pin "P$GND") (pinfunction "GND_P$GND") (pintype "bidirectional"))
      (node (ref "LED_MASK") (pin "P$GND0") (pinfunction "GND0_P$GND0") (pintype "bidirectional"))
      (node (ref "LED_MASK") (pin "P$GND1") (pinfunction "GND1_P$GND1") (pintype "bidirectional"))
      (node (ref "LICK") (pin "P$GND0") (pinfunction "GND0_P$GND0") (pintype "bidirectional"))
      (node (ref "LICK") (pin "P$GND1") (pinfunction "GND1_P$GND1") (pintype "bidirectional"))
      (node (ref "MXP-A") (pin "12") (pinfunction "KL_12") (pintype "passive"))
      (node (ref "MXP-A") (pin "16") (pinfunction "KL_16") (pintype "passive"))
      (node (ref "MXP-A") (pin "20") (pinfunction "KL_20") (pintype "passive"))
      (node (ref "MXP-A") (pin "24") (pinfunction "KL_24") (pintype "passive"))
      (node (ref "MXP-A") (pin "28") (pinfunction "KL_28") (pintype "passive"))
      (node (ref "MXP-A") (pin "30") (pinfunction "KL_30") (pintype "passive"))
      (node (ref "MXP-A") (pin "8") (pinfunction "KL_8") (pintype "passive"))
      (node (ref "MXP-B") (pin "12") (pinfunction "KL_12") (pintype "passive"))
      (node (ref "MXP-B") (pin "16") (pinfunction "KL_16") (pintype "passive"))
      (node (ref "MXP-B") (pin "20") (pinfunction "KL_20") (pintype "passive"))
      (node (ref "MXP-B") (pin "24") (pinfunction "KL_24") (pintype "passive"))
      (node (ref "MXP-B") (pin "28") (pinfunction "KL_28") (pintype "passive"))
      (node (ref "MXP-B") (pin "30") (pinfunction "KL_30") (pintype "passive"))
      (node (ref "MXP-B") (pin "8") (pinfunction "KL_8") (pintype "passive"))
      (node (ref "POWER_LED") (pin "K") (pinfunction "C_K") (pintype "passive"))
      (node (ref "Q10") (pin "E") (pinfunction "E_E") (pintype "passive"))
      (node (ref "Q6") (pin "E") (pinfunction "E_E") (pintype "passive"))
      (node (ref "Q8") (pin "E") (pinfunction "E_E") (pintype "passive"))
      (node (ref "R22") (pin "1") (pinfunction "1_1") (pintype "passive"))
      (node (ref "R25") (pin "1") (pinfunction "1_1") (pintype "passive"))
      (node (ref "R28") (pin "1") (pinfunction "1_1") (pintype "passive"))
      (node (ref "R30") (pin "1") (pinfunction "1_1") (pintype "passive"))
      (node (ref "R31") (pin "1") (pinfunction "1_1") (pintype "passive"))
      (node (ref "R34") (pin "1") (pinfunction "1_1") (pintype "passive"))
      (node (ref "SHUTTER") (pin "P$GND0") (pinfunction "GND0_P$GND0") (pintype "bidirectional"))
      (node (ref "SHUTTER") (pin "P$GND1") (pinfunction "GND1_P$GND1") (pintype "bidirectional"))
      (node (ref "SLN") (pin "P$GND0") (pinfunction "GND0_P$GND0") (pintype "bidirectional"))
      (node (ref "SLN") (pin "P$GND1") (pinfunction "GND1_P$GND1") (pintype "bidirectional"))
      (node (ref "T1") (pin "3") (pinfunction "S_3") (pintype "passive"))
      (node (ref "T2") (pin "3") (pinfunction "S_3") (pintype "passive"))
      (node (ref "U3") (pin "4") (pinfunction "GND_4") (pintype "passive"))
    )
    (net (code "57") (name "GND-ISO") (class "Default")
      (node (ref "BAT1") (pin "-") (pinfunction "-_-") (pintype "power_in"))
      (node (ref "C10") (pin "2") (pinfunction "2_2") (pintype "passive"))
      (node (ref "GND-ISO") (pin "TP") (pinfunction "TP_TP") (pintype "input"))
      (node (ref "JP3") (pin "3") (pinfunction "3_3") (pintype "passive"))
      (node (ref "JP4") (pin "3") (pinfunction "3_3") (pintype "passive"))
      (node (ref "OK3") (pin "2") (pinfunction "C_2") (pintype "passive"))
      (node (ref "OK4") (pin "2") (pinfunction "C_2") (pintype "passive"))
      (node (ref "R16") (pin "E") (pinfunction "E_E") (pintype "passive"))
      (node (ref "R16") (pin "S") (pinfunction "S_S") (pintype "passive"))
      (node (ref "R21") (pin "E") (pinfunction "E_E") (pintype "passive"))
      (node (ref "R21") (pin "S") (pinfunction "S_S") (pintype "passive"))
      (node (ref "R36") (pin "1") (pinfunction "1_1") (pintype "passive"))
      (node (ref "R40") (pin "1") (pinfunction "1_1") (pintype "passive"))
      (node (ref "S3") (pin "5") (pinfunction "P2_5") (pintype "passive"))
      (node (ref "U1") (pin "P1") (pinfunction "P$1_P1") (pintype "bidirectional"))
      (node (ref "U2") (pin "12") (pinfunction "GND_12") (pintype "power_in"))
      (node (ref "U2") (pin "6") (pinfunction "-IN_6") (pintype "input"))
      (node (ref "U2") (pin "7") (pinfunction "+IN_7") (pintype "input"))
      (node (ref "U2") (pin "8") (pinfunction "-IN_8") (pintype "input"))
      (node (ref "U2") (pin "9") (pinfunction "+IN_9") (pintype "input"))
    )
    (net (code "58") (name "LICK_A0_IN") (class "Default")
      (node (ref "JP4") (pin "1") (pinfunction "1_1") (pintype "passive"))
      (node (ref "Q1") (pin "1") (pinfunction "G_1") (pintype "passive"))
      (node (ref "R3") (pin "1") (pinfunction "1_1") (pintype "passive"))
      (node (ref "U1") (pin "P2") (pinfunction "P$2_P2") (pintype "bidirectional"))
    )
    (net (code "59") (name "LICK_A0_OUT") (class "Default")
      (node (ref "C5") (pin "1") (pinfunction "1_1") (pintype "passive"))
      (node (ref "JP7") (pin "3") (pinfunction "3_3") (pintype "passive"))
      (node (ref "OK3") (pin "4") (pinfunction "EMI_4") (pintype "passive"))
      (node (ref "R25") (pin "2") (pinfunction "2_2") (pintype "passive"))
    )
    (net (code "60") (name "LICK_A1_IN") (class "Default")
      (node (ref "JP4") (pin "2") (pinfunction "2_2") (pintype "passive"))
      (node (ref "Q3") (pin "1") (pinfunction "G_1") (pintype "passive"))
      (node (ref "R1") (pin "1") (pinfunction "1_1") (pintype "passive"))
      (node (ref "U1") (pin "P3") (pinfunction "P$3_P3") (pintype "bidirectional"))
    )
    (net (code "61") (name "LICK_A1_OUT") (class "Default")
      (node (ref "C4") (pin "1") (pinfunction "1_1") (pintype "passive"))
      (node (ref "JP8") (pin "3") (pinfunction "3_3") (pintype "passive"))
      (node (ref "OK4") (pin "4") (pinfunction "EMI_4") (pintype "passive"))
      (node (ref "R34") (pin "2") (pinfunction "2_2") (pintype "passive"))
    )
    (net (code "62") (name "LICK_B0_IN") (class "Default")
      (node (ref "JP3") (pin "1") (pinfunction "1_1") (pintype "passive"))
      (node (ref "R38") (pin "1") (pinfunction "1_1") (pintype "passive"))
      (node (ref "U2") (pin "4") (pinfunction "-IN_4") (pintype "input"))
    )
    (net (code "63") (name "LICK_B0_OUT") (class "Default")
      (node (ref "C8") (pin "1") (pinfunction "1_1") (pintype "passive"))
      (node (ref "JP7") (pin "1") (pinfunction "1_1") (pintype "passive"))
      (node (ref "OK1") (pin "4") (pinfunction "EMI_4") (pintype "passive"))
      (node (ref "R22") (pin "2") (pinfunction "2_2") (pintype "passive"))
    )
    (net (code "64") (name "LICK_B1_IN") (class "Default")
      (node (ref "JP3") (pin "2") (pinfunction "2_2") (pintype "passive"))
      (node (ref "R42") (pin "1") (pinfunction "1_1") (pintype "passive"))
      (node (ref "U2") (pin "10") (pinfunction "-IN_10") (pintype "input"))
    )
    (net (code "65") (name "LICK_B1_OUT") (class "Default")
      (node (ref "C9") (pin "1") (pinfunction "1_1") (pintype "passive"))
      (node (ref "JP8") (pin "1") (pinfunction "1_1") (pintype "passive"))
      (node (ref "OK2") (pin "4") (pinfunction "EMI_4") (pintype "passive"))
      (node (ref "R28") (pin "2") (pinfunction "2_2") (pintype "passive"))
    )
    (net (code "66") (name "LICK_DETECT_A0") (class "Default")
      (node (ref "OK1") (pin "2") (pinfunction "C_2") (pintype "passive"))
      (node (ref "R23") (pin "A") (pinfunction "A_A") (pintype "passive"))
      (node (ref "R35") (pin "1") (pinfunction "1_1") (pintype "passive"))
      (node (ref "U2") (pin "2") (pinfunction "OUT_2") (pintype "open_collector"))
    )
    (net (code "67") (name "LICK_DETECT_A1") (class "Default")
      (node (ref "OK2") (pin "2") (pinfunction "C_2") (pintype "passive"))
      (node (ref "R26") (pin "A") (pinfunction "A_A") (pintype "passive"))
      (node (ref "R39") (pin "1") (pinfunction "1_1") (pintype "passive"))
      (node (ref "U2") (pin "13") (pinfunction "OUT_13") (pintype "open_collector"))
    )
    (net (code "68") (name "N$6") (class "Default")
      (node (ref "R31") (pin "2") (pinfunction "2_2") (pintype "passive"))
      (node (ref "R4") (pin "2") (pinfunction "2_2") (pintype "passive"))
      (node (ref "T1") (pin "1") (pinfunction "G_1") (pintype "passive"))
    )
    (net (code "69") (name "N$16") (class "Default")
      (node (ref "BUCKPUCK1") (pin "VIN+") (pinfunction "VIN+_VIN+") (pintype "bidirectional"))
      (node (ref "BUCKPUCK2") (pin "VIN+") (pinfunction "VIN+_VIN+") (pintype "bidirectional"))
      (node (ref "BUCKPUCK3") (pin "VIN+") (pinfunction "VIN+_VIN+") (pintype "bidirectional"))
      (node (ref "C1") (pin "+") (pinfunction "+_+") (pintype "passive"))
      (node (ref "C2") (pin "+") (pinfunction "+_+") (pintype "passive"))
      (node (ref "C3") (pin "+") (pinfunction "+_+") (pintype "passive"))
      (node (ref "C7") (pin "+") (pinfunction "+_+") (pintype "passive"))
      (node (ref "D1") (pin "C") (pinfunction "C_C") (pintype "passive"))
      (node (ref "U3") (pin "1") (pinfunction "VI_1") (pintype "input"))
      (node (ref "VIN") (pin "TP") (pinfunction "TP_TP") (pintype "input"))
    )
    (net (code "70") (name "Net-(AUDIO-GND0)") (class "Default")
      (node (ref "AUDIO") (pin "P$GND0") (pinfunction "GND0_P$GND0") (pintype "bidirectional"))
      (node (ref "AUDIO") (pin "P$GND1") (pinfunction "GND1_P$GND1") (pintype "bidirectional"))
      (node (ref "JP1") (pin "SLEEVE") (pinfunction "SLEEVE_SLEEVE") (pintype "bidirectional"))
      (node (ref "JP2") (pin "SLEEVE") (pinfunction "SLEEVE_SLEEVE") (pintype "bidirectional"))
    )
    (net (code "71") (name "Net-(AUDIO-SIG0)") (class "Default")
      (node (ref "AUDIO") (pin "P$SIG0") (pinfunction "SIG0_P$SIG0") (pintype "bidirectional"))
      (node (ref "JP1") (pin "RING") (pinfunction "RIGHT_RING") (pintype "bidirectional"))
      (node (ref "JP2") (pin "RING") (pinfunction "RIGHT_RING") (pintype "bidirectional"))
    )
    (net (code "72") (name "Net-(AUDIO-SIG1)") (class "Default")
      (node (ref "AUDIO") (pin "P$SIG1") (pinfunction "SIG1_P$SIG1") (pintype "bidirectional"))
      (node (ref "JP1") (pin "TIP") (pinfunction "LEFT_TIP") (pintype "bidirectional"))
      (node (ref "JP2") (pin "TIP") (pinfunction "LEFT_TIP") (pintype "bidirectional"))
    )
    (net (code "73") (name "Net-(BUCKPUCK1-PadCTRL)") (class "Default")
      (node (ref "BUCKPUCK1") (pin "CTRL") (pinfunction "CTRL_CTRL") (pintype "bidirectional"))
      (node (ref "Q5") (pin "C") (pinfunction "C_C") (pintype "passive"))
    )
    (net (code "74") (name "Net-(BUCKPUCK1-PadREF)") (class "Default")
      (node (ref "BUCKPUCK1") (pin "REF") (pinfunction "REF_REF") (pintype "bidirectional"))
      (node (ref "Q5") (pin "E") (pinfunction "E_E") (pintype "passive"))
      (node (ref "R13") (pin "1") (pinfunction "1_1") (pintype "passive"))
    )
    (net (code "75") (name "Net-(BUCKPUCK2-PadCTRL)") (class "Default")
      (node (ref "BUCKPUCK2") (pin "CTRL") (pinfunction "CTRL_CTRL") (pintype "bidirectional"))
      (node (ref "Q7") (pin "C") (pinfunction "C_C") (pintype "passive"))
    )
    (net (code "76") (name "Net-(BUCKPUCK2-PadREF)") (class "Default")
      (node (ref "BUCKPUCK2") (pin "REF") (pinfunction "REF_REF") (pintype "bidirectional"))
      (node (ref "Q7") (pin "E") (pinfunction "E_E") (pintype "passive"))
      (node (ref "R11") (pin "1") (pinfunction "1_1") (pintype "passive"))
    )
    (net (code "77") (name "Net-(BUCKPUCK3-PadCTRL)") (class "Default")
      (node (ref "BUCKPUCK3") (pin "CTRL") (pinfunction "CTRL_CTRL") (pintype "bidirectional"))
      (node (ref "Q9") (pin "C") (pinfunction "C_C") (pintype "passive"))
    )
    (net (code "78") (name "Net-(BUCKPUCK3-PadREF)") (class "Default")
      (node (ref "BUCKPUCK3") (pin "REF") (pinfunction "REF_REF") (pintype "bidirectional"))
      (node (ref "Q9") (pin "E") (pinfunction "E_E") (pintype "passive"))
      (node (ref "R9") (pin "1") (pinfunction "1_1") (pintype "passive"))
    )
    (net (code "79") (name "Net-(CH1-1)") (class "Default")
      (node (ref "BUCKPUCK1") (pin "LED+") (pinfunction "LED+_LED+") (pintype "bidirectional"))
      (node (ref "CH1") (pin "P1") (pinfunction "1_P1") (pintype "passive"))
    )
    (net (code "80") (name "Net-(CH2-1)") (class "Default")
      (node (ref "BUCKPUCK2") (pin "LED+") (pinfunction "LED+_LED+") (pintype "bidirectional"))
      (node (ref "CH2") (pin "P1") (pinfunction "1_P1") (pintype "passive"))
    )
    (net (code "81") (name "Net-(CH3-1)") (class "Default")
      (node (ref "BUCKPUCK3") (pin "LED+") (pinfunction "LED+_LED+") (pintype "bidirectional"))
      (node (ref "CH3") (pin "P1") (pinfunction "1_P1") (pintype "passive"))
    )
    (net (code "82") (name "Net-(D2-C)") (class "Default")
      (node (ref "D2") (pin "A") (pinfunction "C_A") (pintype "passive"))
      (node (ref "J1") (pin "2") (pinfunction "2_2") (pintype "passive"))
      (node (ref "T1") (pin "2") (pinfunction "D_2") (pintype "passive"))
      (node (ref "T1") (pin "4") (pinfunction "D_4") (pintype "passive"))
    )
    (net (code "83") (name "Net-(D3-C)") (class "Default")
      (node (ref "D3") (pin "A") (pinfunction "C_A") (pintype "passive"))
      (node (ref "J2") (pin "2") (pinfunction "2_2") (pintype "passive"))
      (node (ref "T2") (pin "2") (pinfunction "D_2") (pintype "passive"))
      (node (ref "T2") (pin "4") (pinfunction "D_4") (pintype "passive"))
    )
    (net (code "84") (name "Net-(ISOLATED-PadA)") (class "Default")
      (node (ref "ISOLATED") (pin "A") (pinfunction "A_A") (pintype "passive"))
      (node (ref "R43") (pin "1") (pinfunction "1_1") (pintype "passive"))
    )
    (net (code "85") (name "Net-(J1-Pad1)") (class "Default")
      (node (ref "J1") (pin "1") (pinfunction "1_1") (pintype "passive"))
      (node (ref "R32") (pin "1") (pinfunction "1_1") (pintype "passive"))
    )
    (net (code "86") (name "Net-(J2-Pad1)") (class "Default")
      (node (ref "J2") (pin "1") (pinfunction "1_1") (pintype "passive"))
      (node (ref "R33") (pin "1") (pinfunction "1_1") (pintype "passive"))
    )
    (net (code "87") (name "Net-(JP10-PadPWR)") (class "Default")
      (node (ref "JP10") (pin "PWR") (pinfunction "PWR_PWR") (pintype "bidirectional"))
      (node (ref "S1") (pin "2") (pinfunction "2_2") (pintype "passive"))
    )
    (net (code "88") (name "Net-(OK1-A)") (class "Default")
      (node (ref "OK1") (pin "1") (pinfunction "A_1") (pintype "passive"))
      (node (ref "R15") (pin "1") (pinfunction "1_1") (pintype "passive"))
    )
    (net (code "89") (name "Net-(OK2-A)") (class "Default")
      (node (ref "OK2") (pin "1") (pinfunction "A_1") (pintype "passive"))
      (node (ref "R20") (pin "1") (pinfunction "1_1") (pintype "passive"))
    )
    (net (code "90") (name "Net-(OK3-A)") (class "Default")
      (node (ref "OK3") (pin "1") (pinfunction "A_1") (pintype "passive"))
      (node (ref "R19") (pin "2") (pinfunction "2_2") (pintype "passive"))
    )
    (net (code "91") (name "Net-(OK4-A)") (class "Default")
      (node (ref "OK4") (pin "1") (pinfunction "A_1") (pintype "passive"))
      (node (ref "R8") (pin "2") (pinfunction "2_2") (pintype "passive"))
    )
    (net (code "92") (name "Net-(POWER_LED-PadA)") (class "Default")
      (node (ref "POWER_LED") (pin "A") (pinfunction "A_A") (pintype "passive"))
      (node (ref "R7") (pin "1") (pinfunction "1_1") (pintype "passive"))
    )
    (net (code "93") (name "Net-(Q1-D)") (class "Default")
      (node (ref "Q1") (pin "3") (pinfunction "D_3") (pintype "passive"))
      (node (ref "R17") (pin "1") (pinfunction "1_1") (pintype "passive"))
      (node (ref "R18") (pin "2") (pinfunction "2_2") (pintype "passive"))
    )
    (net (code "94") (name "Net-(Q1-S)") (class "Default")
      (node (ref "Q1") (pin "2") (pinfunction "S_2") (pintype "passive"))
      (node (ref "R21") (pin "A") (pinfunction "A_A") (pintype "passive"))
    )
    (net (code "95") (name "Net-(Q2-PadB)") (class "Default")
      (node (ref "Q2") (pin "B") (pinfunction "B_B") (pintype "passive"))
      (node (ref "R18") (pin "1") (pinfunction "1_1") (pintype "passive"))
    )
    (net (code "96") (name "Net-(Q2-PadC)") (class "Default")
      (node (ref "Q2") (pin "C") (pinfunction "C_C") (pintype "passive"))
      (node (ref "R19") (pin "1") (pinfunction "1_1") (pintype "passive"))
    )
    (net (code "97") (name "Net-(Q3-D)") (class "Default")
      (node (ref "Q3") (pin "3") (pinfunction "D_3") (pintype "passive"))
      (node (ref "R5") (pin "1") (pinfunction "1_1") (pintype "passive"))
      (node (ref "R6") (pin "2") (pinfunction "2_2") (pintype "passive"))
    )
    (net (code "98") (name "Net-(Q3-S)") (class "Default")
      (node (ref "Q3") (pin "2") (pinfunction "S_2") (pintype "passive"))
      (node (ref "R16") (pin "A") (pinfunction "A_A") (pintype "passive"))
    )
    (net (code "99") (name "Net-(Q4-PadB)") (class "Default")
      (node (ref "Q4") (pin "B") (pinfunction "B_B") (pintype "passive"))
      (node (ref "R6") (pin "1") (pinfunction "1_1") (pintype "passive"))
    )
    (net (code "100") (name "Net-(Q4-PadC)") (class "Default")
      (node (ref "Q4") (pin "C") (pinfunction "C_C") (pintype "passive"))
      (node (ref "R8") (pin "1") (pinfunction "1_1") (pintype "passive"))
    )
    (net (code "101") (name "Net-(Q5-PadB)") (class "Default")
      (node (ref "Q5") (pin "B") (pinfunction "B_B") (pintype "passive"))
      (node (ref "R13") (pin "2") (pinfunction "2_2") (pintype "passive"))
      (node (ref "R14") (pin "1") (pinfunction "1_1") (pintype "passive"))
    )
    (net (code "102") (name "Net-(Q6-PadB)") (class "Default")
      (node (ref "Q6") (pin "B") (pinfunction "B_B") (pintype "passive"))
      (node (ref "R29") (pin "1") (pinfunction "1_1") (pintype "passive"))
    )
    (net (code "103") (name "Net-(Q6-PadC)") (class "Default")
      (node (ref "Q6") (pin "C") (pinfunction "C_C") (pintype "passive"))
      (node (ref "R14") (pin "2") (pinfunction "2_2") (pintype "passive"))
    )
    (net (code "104") (name "Net-(Q7-PadB)") (class "Default")
      (node (ref "Q7") (pin "B") (pinfunction "B_B") (pintype "passive"))
      (node (ref "R11") (pin "2") (pinfunction "2_2") (pintype "passive"))
      (node (ref "R12") (pin "1") (pinfunction "1_1") (pintype "passive"))
    )
    (net (code "105") (name "Net-(Q8-PadB)") (class "Default")
      (node (ref "Q8") (pin "B") (pinfunction "B_B") (pintype "passive"))
      (node (ref "R27") (pin "1") (pinfunction "1_1") (pintype "passive"))
    )
    (net (code "106") (name "Net-(Q8-PadC)") (class "Default")
      (node (ref "Q8") (pin "C") (pinfunction "C_C") (pintype "passive"))
      (node (ref "R12") (pin "2") (pinfunction "2_2") (pintype "passive"))
    )
    (net (code "107") (name "Net-(Q9-PadB)") (class "Default")
      (node (ref "Q9") (pin "B") (pinfunction "B_B") (pintype "passive"))
      (node (ref "R10") (pin "1") (pinfunction "1_1") (pintype "passive"))
      (node (ref "R9") (pin "2") (pinfunction "2_2") (pintype "passive"))
    )
    (net (code "108") (name "Net-(Q10-PadB)") (class "Default")
      (node (ref "Q10") (pin "B") (pinfunction "B_B") (pintype "passive"))
      (node (ref "R24") (pin "1") (pinfunction "1_1") (pintype "passive"))
    )
    (net (code "109") (name "Net-(Q10-PadC)") (class "Default")
      (node (ref "Q10") (pin "C") (pinfunction "C_C") (pintype "passive"))
      (node (ref "R10") (pin "2") (pinfunction "2_2") (pintype "passive"))
    )
    (net (code "110") (name "Net-(S3-P3)") (class "Default")
      (node (ref "BAT1") (pin "+") (pinfunction "+_+") (pintype "power_in"))
      (node (ref "S3") (pin "8") (pinfunction "P3_8") (pintype "passive"))
    )
    (net (code "111") (name "Net-(S3-S1)") (class "Default")
      (node (ref "R43") (pin "2") (pinfunction "2_2") (pintype "passive"))
      (node (ref "S3") (pin "3") (pinfunction "S1_3") (pintype "passive"))
    )
    (net (code "112") (name "Net-(T2-G)") (class "Default")
      (node (ref "R2") (pin "2") (pinfunction "2_2") (pintype "passive"))
      (node (ref "R30") (pin "2") (pinfunction "2_2") (pintype "passive"))
      (node (ref "T2") (pin "1") (pinfunction "G_1") (pintype "passive"))
    )
    (net (code "113") (name "Net-(U2A-+IN)") (class "Default")
      (node (ref "R23") (pin "E") (pinfunction "E_E") (pintype "passive"))
      (node (ref "R23") (pin "S") (pinfunction "S_S") (pintype "passive"))
      (node (ref "R36") (pin "2") (pinfunction "2_2") (pintype "passive"))
      (node (ref "R37") (pin "1") (pinfunction "1_1") (pintype "passive"))
      (node (ref "U2") (pin "5") (pinfunction "+IN_5") (pintype "input"))
    )
    (net (code "114") (name "Net-(U2D-+IN)") (class "Default")
      (node (ref "R26") (pin "E") (pinfunction "E_E") (pintype "passive"))
      (node (ref "R26") (pin "S") (pinfunction "S_S") (pintype "passive"))
      (node (ref "R40") (pin "2") (pinfunction "2_2") (pintype "passive"))
      (node (ref "R41") (pin "1") (pinfunction "1_1") (pintype "passive"))
      (node (ref "U2") (pin "11") (pinfunction "+IN_11") (pintype "input"))
    )
    (net (code "115") (name "VCC") (class "Default")
      (node (ref "C6") (pin "+") (pinfunction "+_+") (pintype "passive"))
      (node (ref "D2") (pin "C") (pinfunction "A_C") (pintype "passive"))
      (node (ref "D3") (pin "C") (pinfunction "A_C") (pintype "passive"))
      (node (ref "R32") (pin "2") (pinfunction "2_2") (pintype "passive"))
      (node (ref "R33") (pin "2") (pinfunction "2_2") (pintype "passive"))
      (node (ref "R7") (pin "2") (pinfunction "2_2") (pintype "passive"))
      (node (ref "U3") (pin "3") (pinfunction "VO_3") (pintype "passive"))
      (node (ref "VSOLN") (pin "TP") (pinfunction "TP_TP") (pintype "input"))
    )
    (net (code "116") (name "VIN") (class "Default")
      (node (ref "D1") (pin "A") (pinfunction "A_A") (pintype "passive"))
      (node (ref "S1") (pin "1") (pinfunction "1_1") (pintype "passive"))
    )
    (net (code "117") (name "unconnected-(OK1-BAS-Pad6)") (class "Default")
      (node (ref "OK1") (pin "6") (pinfunction "BAS_6") (pintype "passive"))
    )
    (net (code "118") (name "unconnected-(OK2-BAS-Pad6)") (class "Default")
      (node (ref "OK2") (pin "6") (pinfunction "BAS_6") (pintype "passive"))
    )
    (net (code "119") (name "unconnected-(OK3-BAS-Pad6)") (class "Default")
      (node (ref "OK3") (pin "6") (pinfunction "BAS_6") (pintype "passive"))
    )
    (net (code "120") (name "unconnected-(OK4-BAS-Pad6)") (class "Default")
      (node (ref "OK4") (pin "6") (pinfunction "BAS_6") (pintype "passive"))
    )
    (net (code "121") (name "unconnected-(S1-Pad3)") (class "Default")
      (node (ref "S1") (pin "3") (pinfunction "3_3") (pintype "passive"))
    )
    (net (code "122") (name "unconnected-(S3-O3-Pad7)") (class "Default")
      (node (ref "S3") (pin "7") (pinfunction "O3_7") (pintype "passive"))
    )
    (net (code "123") (name "unconnected-(S3-S2-Pad6)") (class "Default")
      (node (ref "S3") (pin "6") (pinfunction "S2_6") (pintype "passive"))
    )
    (net (code "124") (name "unconnected-(U2B-OUT-Pad1)") (class "Default")
      (node (ref "U2") (pin "1") (pinfunction "OUT_1") (pintype "open_collector"))
    )
    (net (code "125") (name "unconnected-(U2C-OUT-Pad14)") (class "Default")
      (node (ref "U2") (pin "14") (pinfunction "OUT_14") (pintype "open_collector"))
    )
  )
)
